# tyraka3_0.net
KiCad netlist of a schematic drawn in EAGLE
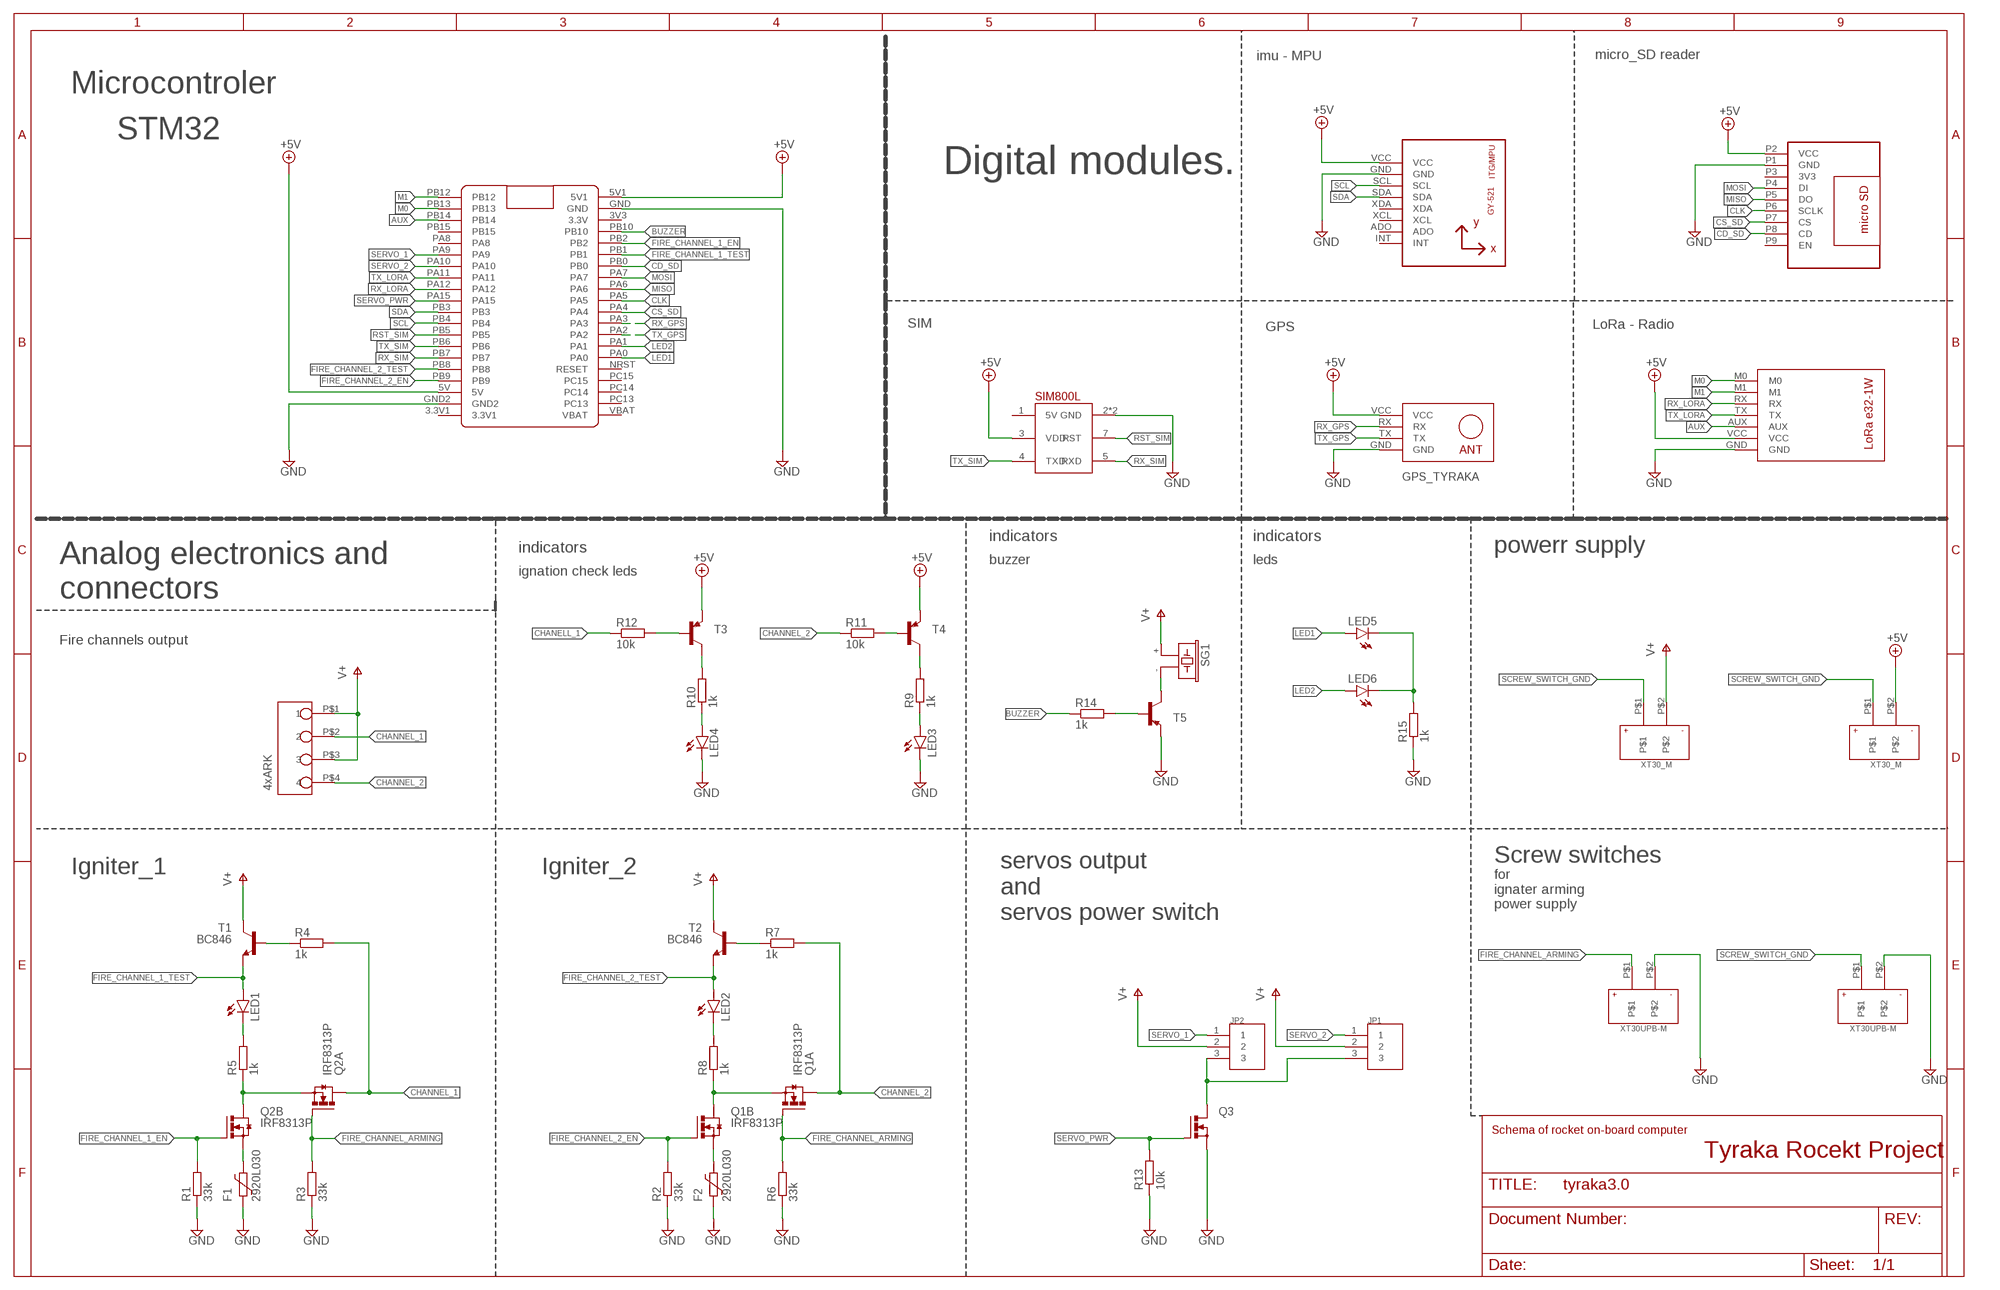
[diagram p0: schematic, sheet 1]

(export (version "E")
  (design (tool "Eeschema 10.0.6"))
  (components
    (comp (ref "F1")
      (value "2920L030")
      (footprint "eagle-import:2920L")
      (fields (field (name "MF") "Littelfuse"))
      (libsource (lib "eagle-import") (part "?2920L030"))
    )
    (comp (ref "F2")
      (value "2920L030")
      (footprint "eagle-import:2920L")
      (fields (field (name "MF") "Littelfuse"))
      (libsource (lib "eagle-import") (part "?2920L030"))
    )
    (comp (ref "JP1")
      (value "3PIN")
      (footprint "eagle-import:B3B-PH-K-S")
      (libsource (lib "eagle-import") (part "3PIN"))
    )
    (comp (ref "JP2")
      (value "3PIN")
      (footprint "eagle-import:B3B-PH-K-S")
      (libsource (lib "eagle-import") (part "3PIN"))
    )
    (comp (ref "LED1")
      (value "LEDCHIP-LED0805")
      (footprint "eagle-import:CHIP-LED0805")
      (libsource (lib "eagle-import") (part "LEDCHIP-LED0805"))
    )
    (comp (ref "LED2")
      (value "LEDCHIP-LED0805")
      (footprint "eagle-import:CHIP-LED0805")
      (libsource (lib "eagle-import") (part "LEDCHIP-LED0805"))
    )
    (comp (ref "LED3")
      (value "LEDCHIP-LED0805")
      (footprint "eagle-import:CHIP-LED0805")
      (libsource (lib "eagle-import") (part "LEDCHIP-LED0805"))
    )
    (comp (ref "LED4")
      (value "LEDCHIP-LED0805")
      (footprint "eagle-import:CHIP-LED0805")
      (libsource (lib "eagle-import") (part "LEDCHIP-LED0805"))
    )
    (comp (ref "LED5")
      (value "LEDCHIP-LED0805")
      (footprint "eagle-import:CHIP-LED0805")
      (libsource (lib "eagle-import") (part "LEDCHIP-LED0805"))
    )
    (comp (ref "LED6")
      (value "LEDCHIP-LED0805")
      (footprint "eagle-import:CHIP-LED0805")
      (libsource (lib "eagle-import") (part "LEDCHIP-LED0805"))
    )
    (comp (ref "Q1")
      (value "IRF8313P")
      (footprint "eagle-import:SO-08")
      (libsource (lib "eagle-import") (part "IRF8313P"))
    )
    (comp (ref "Q2")
      (value "IRF8313P")
      (footprint "eagle-import:SO-08")
      (libsource (lib "eagle-import") (part "IRF8313P"))
    )
    (comp (ref "Q3")
      (value "N-MOSFET-SO8S")
      (footprint "eagle-import:SO-08")
      (libsource (lib "eagle-import") (part "N-MOSFET-SO8S"))
    )
    (comp (ref "R1")
      (value "33k")
      (footprint "eagle-import:R0805")
      (libsource (lib "eagle-import") (part "R-EU_R0805"))
    )
    (comp (ref "R2")
      (value "33k")
      (footprint "eagle-import:R0805")
      (libsource (lib "eagle-import") (part "R-EU_R0805"))
    )
    (comp (ref "R3")
      (value "33k")
      (footprint "eagle-import:R0805")
      (libsource (lib "eagle-import") (part "R-EU_R0805"))
    )
    (comp (ref "R4")
      (value "1k")
      (footprint "eagle-import:R0805")
      (libsource (lib "eagle-import") (part "R-EU_R0805"))
    )
    (comp (ref "R5")
      (value "1k")
      (footprint "eagle-import:R0805")
      (libsource (lib "eagle-import") (part "R-EU_R0805"))
    )
    (comp (ref "R6")
      (value "33k")
      (footprint "eagle-import:R0805")
      (libsource (lib "eagle-import") (part "R-EU_R0805"))
    )
    (comp (ref "R7")
      (value "1k")
      (footprint "eagle-import:R0805")
      (libsource (lib "eagle-import") (part "R-EU_R0805"))
    )
    (comp (ref "R8")
      (value "1k")
      (footprint "eagle-import:R0805")
      (libsource (lib "eagle-import") (part "R-EU_R0805"))
    )
    (comp (ref "R9")
      (value "1k")
      (footprint "eagle-import:R0805")
      (libsource (lib "eagle-import") (part "R-EU_R0805"))
    )
    (comp (ref "R10")
      (value "1k")
      (footprint "eagle-import:R0805")
      (libsource (lib "eagle-import") (part "R-EU_R0805"))
    )
    (comp (ref "R11")
      (value "10k")
      (footprint "eagle-import:R0805")
      (libsource (lib "eagle-import") (part "R-EU_R0805"))
    )
    (comp (ref "R12")
      (value "10k")
      (footprint "eagle-import:R0805")
      (libsource (lib "eagle-import") (part "R-EU_R0805"))
    )
    (comp (ref "R13")
      (value "10k")
      (footprint "eagle-import:R0805")
      (libsource (lib "eagle-import") (part "R-EU_R0805"))
    )
    (comp (ref "R14")
      (value "1k")
      (footprint "eagle-import:R0805")
      (libsource (lib "eagle-import") (part "R-EU_R0805"))
    )
    (comp (ref "R15")
      (value "1k")
      (footprint "eagle-import:R0805")
      (libsource (lib "eagle-import") (part "R-EU_R0805"))
    )
    (comp (ref "SD1")
      (value "MICRO_SD")
      (footprint "eagle-import:MICRO_SD")
      (libsource (lib "eagle-import") (part "MICRO_SD"))
    )
    (comp (ref "SG1")
      (value "F/CM12P")
      (footprint "eagle-import:F_CM12P")
      (libsource (lib "eagle-import") (part "F/CM12P"))
    )
    (comp (ref "T1")
      (value "BC846")
      (footprint "eagle-import:SOT23")
      (libsource (lib "eagle-import") (part "BC846"))
    )
    (comp (ref "T2")
      (value "BC846")
      (footprint "eagle-import:SOT23")
      (libsource (lib "eagle-import") (part "BC846"))
    )
    (comp (ref "T3")
      (value "BC856A-PNP-SOT23-BEC")
      (footprint "eagle-import:SOT23-BEC")
      (libsource (lib "eagle-import") (part "-PNP-SOT23-BECBC856A"))
    )
    (comp (ref "T4")
      (value "BC856A-PNP-SOT23-BEC")
      (footprint "eagle-import:SOT23-BEC")
      (libsource (lib "eagle-import") (part "-PNP-SOT23-BECBC856A"))
    )
    (comp (ref "T5")
      (value "BC856A-PNP-SOT23-BEC")
      (footprint "eagle-import:SOT23-BEC")
      (libsource (lib "eagle-import") (part "-PNP-SOT23-BECBC856A"))
    )
    (comp (ref "U$1")
      (value "SIM800L")
      (footprint "eagle-import:SIP")
      (libsource (lib "eagle-import") (part "SIM800L"))
    )
    (comp (ref "U$2")
      (value "LORA_E32")
      (footprint "eagle-import:LORA_E32")
      (libsource (lib "eagle-import") (part "LORA_E32"))
    )
    (comp (ref "U$3")
      (value "BLUE_PILL")
      (footprint "eagle-import:BLUE_PILL")
      (libsource (lib "eagle-import") (part "BLUE_PILL"))
    )
    (comp (ref "U$4")
      (value "GPS_TYRAKA")
      (footprint "eagle-import:GPS-RECEIVER-NEO6M")
      (libsource (lib "eagle-import") (part "GPS_TYRAKA"))
    )
    (comp (ref "U$5")
      (value "XT30_MALE_90")
      (footprint "eagle-import:XT60_MALE_90")
      (libsource (lib "eagle-import") (part "XT30_MALE_90"))
    )
    (comp (ref "U$6")
      (value "XT30_MALE_90")
      (footprint "eagle-import:XT60_MALE_90")
      (libsource (lib "eagle-import") (part "XT30_MALE_90"))
    )
    (comp (ref "U$7")
      (value "4X_ARK_8.5MM")
      (footprint "eagle-import:4XZLACZESRUBOWE")
      (libsource (lib "eagle-import") (part "4X_ARK_8.5MM"))
    )
    (comp (ref "U$8")
      (value "XT30UPB-M")
      (footprint "eagle-import:XT30UPB-M")
      (libsource (lib "eagle-import") (part "XT30UPB-M"))
    )
    (comp (ref "U$9")
      (value "XT30UPB-M")
      (footprint "eagle-import:XT30UPB-M")
      (libsource (lib "eagle-import") (part "XT30UPB-M"))
    )
    (comp (ref "U2")
      (value "GY-521MPU6050")
      (footprint "eagle-import:GY-521")
      (libsource (lib "eagle-import") (part "GY-521MPU6050"))
    )
  )
  (nets
    (net (code "1") (name "+5V") (class "Default")
      (node (ref "SD1") (pin "P2") (pinfunction "VCC_P2") (pintype "power_in"))
      (node (ref "T3") (pin "E") (pinfunction "E_E") (pintype "passive"))
      (node (ref "T4") (pin "E") (pinfunction "E_E") (pintype "passive"))
      (node (ref "U$1") (pin "3") (pinfunction "VDD_3") (pintype "bidirectional"))
      (node (ref "U$2") (pin "VCC") (pinfunction "VCC_VCC") (pintype "bidirectional"))
      (node (ref "U$3") (pin "5V") (pinfunction "5V_5V") (pintype "bidirectional"))
      (node (ref "U$3") (pin "5V1") (pinfunction "5V1_5V1") (pintype "power_in"))
      (node (ref "U$4") (pin "VCC") (pinfunction "VCC_VCC") (pintype "power_in"))
      (node (ref "U$6") (pin "P$2") (pinfunction "P$2_P$2") (pintype "bidirectional"))
      (node (ref "U2") (pin "VCC") (pinfunction "VCC_VCC") (pintype "bidirectional"))
    )
    (net (code "2") (name "AUX") (class "Default")
      (node (ref "U$2") (pin "AUX") (pinfunction "AUX_AUX") (pintype "bidirectional"))
      (node (ref "U$3") (pin "PB14") (pinfunction "PB14_PB14") (pintype "bidirectional"))
    )
    (net (code "3") (name "BUZZER") (class "Default")
      (node (ref "R14") (pin "1") (pinfunction "1_1") (pintype "passive"))
      (node (ref "U$3") (pin "PB10") (pinfunction "PB10_PB10") (pintype "bidirectional"))
    )
    (net (code "4") (name "CD_SD") (class "Default")
      (node (ref "SD1") (pin "P8") (pinfunction "CD_P8") (pintype "bidirectional"))
      (node (ref "U$3") (pin "PB0") (pinfunction "PB0_PB0") (pintype "bidirectional"))
    )
    (net (code "5") (name "CHANELL_1") (class "Default")
      (node (ref "R12") (pin "1") (pinfunction "1_1") (pintype "passive"))
    )
    (net (code "6") (name "CHANNEL_1") (class "Default")
      (node (ref "Q2") (pin "5") (pinfunction "D_5") (pintype "passive"))
      (node (ref "Q2") (pin "6") (pinfunction "D_6") (pintype "passive"))
      (node (ref "R4") (pin "2") (pinfunction "2_2") (pintype "passive"))
      (node (ref "U$7") (pin "P$2") (pinfunction "2_P$2") (pintype "bidirectional"))
    )
    (net (code "7") (name "CHANNEL_2") (class "Default")
      (node (ref "Q1") (pin "5") (pinfunction "D_5") (pintype "passive"))
      (node (ref "Q1") (pin "6") (pinfunction "D_6") (pintype "passive"))
      (node (ref "R11") (pin "1") (pinfunction "1_1") (pintype "passive"))
      (node (ref "R7") (pin "2") (pinfunction "2_2") (pintype "passive"))
      (node (ref "U$7") (pin "P$4") (pinfunction "4_P$4") (pintype "bidirectional"))
    )
    (net (code "8") (name "CLK") (class "Default")
      (node (ref "SD1") (pin "P6") (pinfunction "SCLK_P6") (pintype "bidirectional"))
      (node (ref "U$3") (pin "PA5") (pinfunction "PA5_PA5") (pintype "bidirectional"))
    )
    (net (code "9") (name "CS_SD") (class "Default")
      (node (ref "SD1") (pin "P7") (pinfunction "CS_P7") (pintype "bidirectional"))
      (node (ref "U$3") (pin "PA4") (pinfunction "PA4_PA4") (pintype "bidirectional"))
    )
    (net (code "10") (name "FIRE_CHANNEL_1_EN") (class "Default")
      (node (ref "Q2") (pin "2") (pinfunction "G_2") (pintype "passive"))
      (node (ref "R1") (pin "2") (pinfunction "2_2") (pintype "passive"))
      (node (ref "U$3") (pin "PB2") (pinfunction "PB2_PB2") (pintype "bidirectional"))
    )
    (net (code "11") (name "FIRE_CHANNEL_1_TEST") (class "Default")
      (node (ref "LED1") (pin "A") (pinfunction "A_A") (pintype "passive"))
      (node (ref "T1") (pin "2") (pinfunction "E_2") (pintype "passive"))
      (node (ref "U$3") (pin "PB1") (pinfunction "PB1_PB1") (pintype "bidirectional"))
    )
    (net (code "12") (name "FIRE_CHANNEL_2_EN") (class "Default")
      (node (ref "Q1") (pin "2") (pinfunction "G_2") (pintype "passive"))
      (node (ref "R2") (pin "2") (pinfunction "2_2") (pintype "passive"))
      (node (ref "U$3") (pin "PB9") (pinfunction "PB9_PB9") (pintype "bidirectional"))
    )
    (net (code "13") (name "FIRE_CHANNEL_2_TEST") (class "Default")
      (node (ref "LED2") (pin "A") (pinfunction "A_A") (pintype "passive"))
      (node (ref "T2") (pin "2") (pinfunction "E_2") (pintype "passive"))
      (node (ref "U$3") (pin "PB8") (pinfunction "PB8_PB8") (pintype "bidirectional"))
    )
    (net (code "14") (name "FIRE_CHANNEL_ARMING") (class "Default")
      (node (ref "Q1") (pin "4") (pinfunction "G_4") (pintype "passive"))
      (node (ref "Q2") (pin "4") (pinfunction "G_4") (pintype "passive"))
      (node (ref "R3") (pin "2") (pinfunction "2_2") (pintype "passive"))
      (node (ref "R6") (pin "2") (pinfunction "2_2") (pintype "passive"))
      (node (ref "U$8") (pin "P$1") (pinfunction "P$1_P$1") (pintype "bidirectional"))
    )
    (net (code "15") (name "GND") (class "Default")
      (node (ref "F1") (pin "2") (pinfunction "2_2") (pintype "passive"))
      (node (ref "F2") (pin "2") (pinfunction "2_2") (pintype "passive"))
      (node (ref "LED3") (pin "C") (pinfunction "C_C") (pintype "passive"))
      (node (ref "LED4") (pin "C") (pinfunction "C_C") (pintype "passive"))
      (node (ref "Q3") (pin "1") (pinfunction "S_1") (pintype "passive"))
      (node (ref "Q3") (pin "2") (pinfunction "S_2") (pintype "passive"))
      (node (ref "Q3") (pin "3") (pinfunction "S_3") (pintype "passive"))
      (node (ref "R1") (pin "1") (pinfunction "1_1") (pintype "passive"))
      (node (ref "R13") (pin "1") (pinfunction "1_1") (pintype "passive"))
      (node (ref "R15") (pin "1") (pinfunction "1_1") (pintype "passive"))
      (node (ref "R2") (pin "1") (pinfunction "1_1") (pintype "passive"))
      (node (ref "R3") (pin "1") (pinfunction "1_1") (pintype "passive"))
      (node (ref "R6") (pin "1") (pinfunction "1_1") (pintype "passive"))
      (node (ref "SD1") (pin "P1") (pinfunction "GND_P1") (pintype "power_in"))
      (node (ref "T5") (pin "E") (pinfunction "E_E") (pintype "passive"))
      (node (ref "U$1") (pin "2") (pinfunction "GND_2") (pintype "bidirectional"))
      (node (ref "U$1") (pin "6") (pinfunction "GND_6") (pintype "bidirectional"))
      (node (ref "U$2") (pin "GND") (pinfunction "GND_GND") (pintype "bidirectional"))
      (node (ref "U$3") (pin "GND") (pinfunction "GND_GND") (pintype "bidirectional"))
      (node (ref "U$3") (pin "GND2") (pinfunction "GND2_GND2") (pintype "bidirectional"))
      (node (ref "U$4") (pin "GND") (pinfunction "GND_GND") (pintype "power_in"))
      (node (ref "U$8") (pin "P$2") (pinfunction "P$2_P$2") (pintype "bidirectional"))
      (node (ref "U$9") (pin "P$2") (pinfunction "P$2_P$2") (pintype "bidirectional"))
      (node (ref "U2") (pin "GND") (pinfunction "GND_GND") (pintype "bidirectional"))
    )
    (net (code "16") (name "LED1") (class "Default")
      (node (ref "LED5") (pin "A") (pinfunction "A_A") (pintype "passive"))
      (node (ref "U$3") (pin "PA0") (pinfunction "PA0_PA0") (pintype "bidirectional"))
    )
    (net (code "17") (name "LED2") (class "Default")
      (node (ref "LED6") (pin "A") (pinfunction "A_A") (pintype "passive"))
      (node (ref "U$3") (pin "PA1") (pinfunction "PA1_PA1") (pintype "bidirectional"))
    )
    (net (code "18") (name "M0") (class "Default")
      (node (ref "U$2") (pin "M0") (pinfunction "M0_M0") (pintype "bidirectional"))
      (node (ref "U$3") (pin "PB13") (pinfunction "PB13_PB13") (pintype "bidirectional"))
    )
    (net (code "19") (name "M1") (class "Default")
      (node (ref "U$2") (pin "M1") (pinfunction "M1_M1") (pintype "bidirectional"))
      (node (ref "U$3") (pin "PB12") (pinfunction "PB12_PB12") (pintype "bidirectional"))
    )
    (net (code "20") (name "MISO") (class "Default")
      (node (ref "SD1") (pin "P5") (pinfunction "DO_P5") (pintype "bidirectional"))
      (node (ref "U$3") (pin "PA6") (pinfunction "PA6_PA6") (pintype "bidirectional"))
    )
    (net (code "21") (name "MOSI") (class "Default")
      (node (ref "SD1") (pin "P4") (pinfunction "DI_P4") (pintype "bidirectional"))
      (node (ref "U$3") (pin "PA7") (pinfunction "PA7_PA7") (pintype "bidirectional"))
    )
    (net (code "22") (name "Net-(JP1-Pad3)") (class "Default")
      (node (ref "JP1") (pin "3") (pinfunction "3_3") (pintype "bidirectional"))
      (node (ref "JP2") (pin "3") (pinfunction "3_3") (pintype "bidirectional"))
      (node (ref "Q3") (pin "5") (pinfunction "D_5") (pintype "passive"))
      (node (ref "Q3") (pin "6") (pinfunction "D_6") (pintype "passive"))
      (node (ref "Q3") (pin "7") (pinfunction "D_7") (pintype "passive"))
      (node (ref "Q3") (pin "8") (pinfunction "D_8") (pintype "passive"))
    )
    (net (code "23") (name "Net-(LED1-PadC)") (class "Default")
      (node (ref "LED1") (pin "C") (pinfunction "C_C") (pintype "passive"))
      (node (ref "R5") (pin "2") (pinfunction "2_2") (pintype "passive"))
    )
    (net (code "24") (name "Net-(LED2-PadC)") (class "Default")
      (node (ref "LED2") (pin "C") (pinfunction "C_C") (pintype "passive"))
      (node (ref "R8") (pin "2") (pinfunction "2_2") (pintype "passive"))
    )
    (net (code "25") (name "Net-(LED3-PadA)") (class "Default")
      (node (ref "LED3") (pin "A") (pinfunction "A_A") (pintype "passive"))
      (node (ref "R9") (pin "1") (pinfunction "1_1") (pintype "passive"))
    )
    (net (code "26") (name "Net-(LED4-PadA)") (class "Default")
      (node (ref "LED4") (pin "A") (pinfunction "A_A") (pintype "passive"))
      (node (ref "R10") (pin "1") (pinfunction "1_1") (pintype "passive"))
    )
    (net (code "27") (name "Net-(LED5-PadC)") (class "Default")
      (node (ref "LED5") (pin "C") (pinfunction "C_C") (pintype "passive"))
      (node (ref "LED6") (pin "C") (pinfunction "C_C") (pintype "passive"))
      (node (ref "R15") (pin "2") (pinfunction "2_2") (pintype "passive"))
    )
    (net (code "28") (name "Net-(Q1A-S)") (class "Default")
      (node (ref "Q1") (pin "3") (pinfunction "S_3") (pintype "passive"))
      (node (ref "Q1") (pin "7") (pinfunction "D_7") (pintype "passive"))
      (node (ref "Q1") (pin "8") (pinfunction "D_8") (pintype "passive"))
      (node (ref "R8") (pin "1") (pinfunction "1_1") (pintype "passive"))
    )
    (net (code "29") (name "Net-(Q1B-S)") (class "Default")
      (node (ref "F2") (pin "1") (pinfunction "1_1") (pintype "passive"))
      (node (ref "Q1") (pin "1") (pinfunction "S_1") (pintype "passive"))
    )
    (net (code "30") (name "Net-(Q2A-S)") (class "Default")
      (node (ref "Q2") (pin "3") (pinfunction "S_3") (pintype "passive"))
      (node (ref "Q2") (pin "7") (pinfunction "D_7") (pintype "passive"))
      (node (ref "Q2") (pin "8") (pinfunction "D_8") (pintype "passive"))
      (node (ref "R5") (pin "1") (pinfunction "1_1") (pintype "passive"))
    )
    (net (code "31") (name "Net-(Q2B-S)") (class "Default")
      (node (ref "F1") (pin "1") (pinfunction "1_1") (pintype "passive"))
      (node (ref "Q2") (pin "1") (pinfunction "S_1") (pintype "passive"))
    )
    (net (code "32") (name "Net-(R9-Pad2)") (class "Default")
      (node (ref "R9") (pin "2") (pinfunction "2_2") (pintype "passive"))
      (node (ref "T4") (pin "C") (pinfunction "C_C") (pintype "passive"))
    )
    (net (code "33") (name "Net-(R10-Pad2)") (class "Default")
      (node (ref "R10") (pin "2") (pinfunction "2_2") (pintype "passive"))
      (node (ref "T3") (pin "C") (pinfunction "C_C") (pintype "passive"))
    )
    (net (code "34") (name "Net-(R11-Pad2)") (class "Default")
      (node (ref "R11") (pin "2") (pinfunction "2_2") (pintype "passive"))
      (node (ref "T4") (pin "B") (pinfunction "B_B") (pintype "passive"))
    )
    (net (code "35") (name "Net-(R12-Pad2)") (class "Default")
      (node (ref "R12") (pin "2") (pinfunction "2_2") (pintype "passive"))
      (node (ref "T3") (pin "B") (pinfunction "B_B") (pintype "passive"))
    )
    (net (code "36") (name "Net-(R14-Pad2)") (class "Default")
      (node (ref "R14") (pin "2") (pinfunction "2_2") (pintype "passive"))
      (node (ref "T5") (pin "B") (pinfunction "B_B") (pintype "passive"))
    )
    (net (code "37") (name "Net-(SG1-2)") (class "Default")
      (node (ref "SG1") (pin "-") (pinfunction "2_-") (pintype "passive"))
      (node (ref "T5") (pin "C") (pinfunction "C_C") (pintype "passive"))
    )
    (net (code "38") (name "Net-(T1-B)") (class "Default")
      (node (ref "R4") (pin "1") (pinfunction "1_1") (pintype "passive"))
      (node (ref "T1") (pin "1") (pinfunction "B_1") (pintype "passive"))
    )
    (net (code "39") (name "Net-(T2-B)") (class "Default")
      (node (ref "R7") (pin "1") (pinfunction "1_1") (pintype "passive"))
      (node (ref "T2") (pin "1") (pinfunction "B_1") (pintype "passive"))
    )
    (net (code "40") (name "RST_SIM") (class "Default")
      (node (ref "U$1") (pin "7") (pinfunction "RST_7") (pintype "bidirectional"))
      (node (ref "U$3") (pin "PB5") (pinfunction "PB5_PB5") (pintype "bidirectional"))
    )
    (net (code "41") (name "RX_GPS") (class "Default")
      (node (ref "U$3") (pin "PA3") (pinfunction "PA3_PA3") (pintype "bidirectional"))
      (node (ref "U$4") (pin "RX") (pinfunction "RX_RX") (pintype "bidirectional"))
    )
    (net (code "42") (name "RX_LORA") (class "Default")
      (node (ref "U$2") (pin "RX") (pinfunction "RX_RX") (pintype "bidirectional"))
      (node (ref "U$3") (pin "PA12") (pinfunction "PA12_PA12") (pintype "bidirectional"))
    )
    (net (code "43") (name "RX_SIM") (class "Default")
      (node (ref "U$1") (pin "5") (pinfunction "RXD_5") (pintype "bidirectional"))
      (node (ref "U$3") (pin "PB7") (pinfunction "PB7_PB7") (pintype "bidirectional"))
    )
    (net (code "44") (name "SCL") (class "Default")
      (node (ref "U$3") (pin "PB4") (pinfunction "PB4_PB4") (pintype "bidirectional"))
      (node (ref "U2") (pin "SCL") (pinfunction "SCL_SCL") (pintype "bidirectional"))
    )
    (net (code "45") (name "SCREW_SWITCH_GND") (class "Default")
      (node (ref "U$5") (pin "P$1") (pinfunction "P$1_P$1") (pintype "bidirectional"))
      (node (ref "U$6") (pin "P$1") (pinfunction "P$1_P$1") (pintype "bidirectional"))
      (node (ref "U$9") (pin "P$1") (pinfunction "P$1_P$1") (pintype "bidirectional"))
    )
    (net (code "46") (name "SDA") (class "Default")
      (node (ref "U$3") (pin "PB3") (pinfunction "PB3_PB3") (pintype "bidirectional"))
      (node (ref "U2") (pin "SDA") (pinfunction "SDA_SDA") (pintype "bidirectional"))
    )
    (net (code "47") (name "SERVO_1") (class "Default")
      (node (ref "JP2") (pin "1") (pinfunction "1_1") (pintype "bidirectional"))
      (node (ref "U$3") (pin "PA9") (pinfunction "PA9_PA9") (pintype "bidirectional"))
    )
    (net (code "48") (name "SERVO_2") (class "Default")
      (node (ref "JP1") (pin "1") (pinfunction "1_1") (pintype "bidirectional"))
      (node (ref "U$3") (pin "PA10") (pinfunction "PA10_PA10") (pintype "bidirectional"))
    )
    (net (code "49") (name "SERVO_PWR") (class "Default")
      (node (ref "Q3") (pin "4") (pinfunction "G_4") (pintype "passive"))
      (node (ref "R13") (pin "2") (pinfunction "2_2") (pintype "passive"))
      (node (ref "U$3") (pin "PA15") (pinfunction "PA15_PA15") (pintype "bidirectional"))
    )
    (net (code "50") (name "TX_GPS") (class "Default")
      (node (ref "U$3") (pin "PA2") (pinfunction "PA2_PA2") (pintype "bidirectional"))
      (node (ref "U$4") (pin "TX") (pinfunction "TX_TX") (pintype "bidirectional"))
    )
    (net (code "51") (name "TX_LORA") (class "Default")
      (node (ref "U$2") (pin "TX") (pinfunction "TX_TX") (pintype "bidirectional"))
      (node (ref "U$3") (pin "PA11") (pinfunction "PA11_PA11") (pintype "bidirectional"))
    )
    (net (code "52") (name "TX_SIM") (class "Default")
      (node (ref "U$1") (pin "4") (pinfunction "TXD_4") (pintype "bidirectional"))
      (node (ref "U$3") (pin "PB6") (pinfunction "PB6_PB6") (pintype "bidirectional"))
    )
    (net (code "53") (name "V+") (class "Default")
      (node (ref "JP1") (pin "2") (pinfunction "2_2") (pintype "bidirectional"))
      (node (ref "JP2") (pin "2") (pinfunction "2_2") (pintype "bidirectional"))
      (node (ref "SG1") (pin "+") (pinfunction "1_+") (pintype "passive"))
      (node (ref "T1") (pin "3") (pinfunction "C_3") (pintype "passive"))
      (node (ref "T2") (pin "3") (pinfunction "C_3") (pintype "passive"))
      (node (ref "U$5") (pin "P$2") (pinfunction "P$2_P$2") (pintype "bidirectional"))
      (node (ref "U$7") (pin "P$1") (pinfunction "1_P$1") (pintype "bidirectional"))
      (node (ref "U$7") (pin "P$3") (pinfunction "3_P$3") (pintype "bidirectional"))
    )
    (net (code "54") (name "unconnected-(SD1-3V3-PadP3)") (class "Default")
      (node (ref "SD1") (pin "P3") (pinfunction "3V3_P3") (pintype "bidirectional"))
    )
    (net (code "55") (name "unconnected-(SD1-EN-PadP9)") (class "Default")
      (node (ref "SD1") (pin "P9") (pinfunction "EN_P9") (pintype "bidirectional"))
    )
    (net (code "56") (name "unconnected-(U$1-5V-Pad1)") (class "Default")
      (node (ref "U$1") (pin "1") (pinfunction "5V_1") (pintype "bidirectional"))
    )
    (net (code "57") (name "unconnected-(U$3-3.3V-Pad3V3)") (class "Default")
      (node (ref "U$3") (pin "3V3") (pinfunction "3.3V_3V3") (pintype "bidirectional"))
    )
    (net (code "58") (name "unconnected-(U$3-Pad3.3V1)") (class "Default")
      (node (ref "U$3") (pin "3.3V1") (pinfunction "3.3V1_3.3V1") (pintype "bidirectional"))
    )
    (net (code "59") (name "unconnected-(U$3-PadPA8)") (class "Default")
      (node (ref "U$3") (pin "PA8") (pinfunction "PA8_PA8") (pintype "bidirectional"))
    )
    (net (code "60") (name "unconnected-(U$3-PadPB15)") (class "Default")
      (node (ref "U$3") (pin "PB15") (pinfunction "PB15_PB15") (pintype "bidirectional"))
    )
    (net (code "61") (name "unconnected-(U$3-PadPC13)") (class "Default")
      (node (ref "U$3") (pin "PC13") (pinfunction "PC13_PC13") (pintype "bidirectional"))
    )
    (net (code "62") (name "unconnected-(U$3-PadPC14)") (class "Default")
      (node (ref "U$3") (pin "PC14") (pinfunction "PC14_PC14") (pintype "bidirectional"))
    )
    (net (code "63") (name "unconnected-(U$3-PadPC15)") (class "Default")
      (node (ref "U$3") (pin "PC15") (pinfunction "PC15_PC15") (pintype "bidirectional"))
    )
    (net (code "64") (name "unconnected-(U$3-PadVBAT)") (class "Default")
      (node (ref "U$3") (pin "VBAT") (pinfunction "VBAT_VBAT") (pintype "bidirectional"))
    )
    (net (code "65") (name "unconnected-(U$3-RESET-PadNRST)") (class "Default")
      (node (ref "U$3") (pin "NRST") (pinfunction "RESET_NRST") (pintype "bidirectional"))
    )
    (net (code "66") (name "unconnected-(U2-PadADO)") (class "Default")
      (node (ref "U2") (pin "ADO") (pinfunction "ADO_ADO") (pintype "bidirectional"))
    )
    (net (code "67") (name "unconnected-(U2-PadINT)") (class "Default")
      (node (ref "U2") (pin "INT") (pinfunction "INT_INT") (pintype "bidirectional"))
    )
    (net (code "68") (name "unconnected-(U2-PadXCL)") (class "Default")
      (node (ref "U2") (pin "XCL") (pinfunction "XCL_XCL") (pintype "bidirectional"))
    )
    (net (code "69") (name "unconnected-(U2-PadXDA)") (class "Default")
      (node (ref "U2") (pin "XDA") (pinfunction "XDA_XDA") (pintype "bidirectional"))
    )
  )
)
